# b10n1c.net
KiCad netlist of a schematic drawn in EAGLE
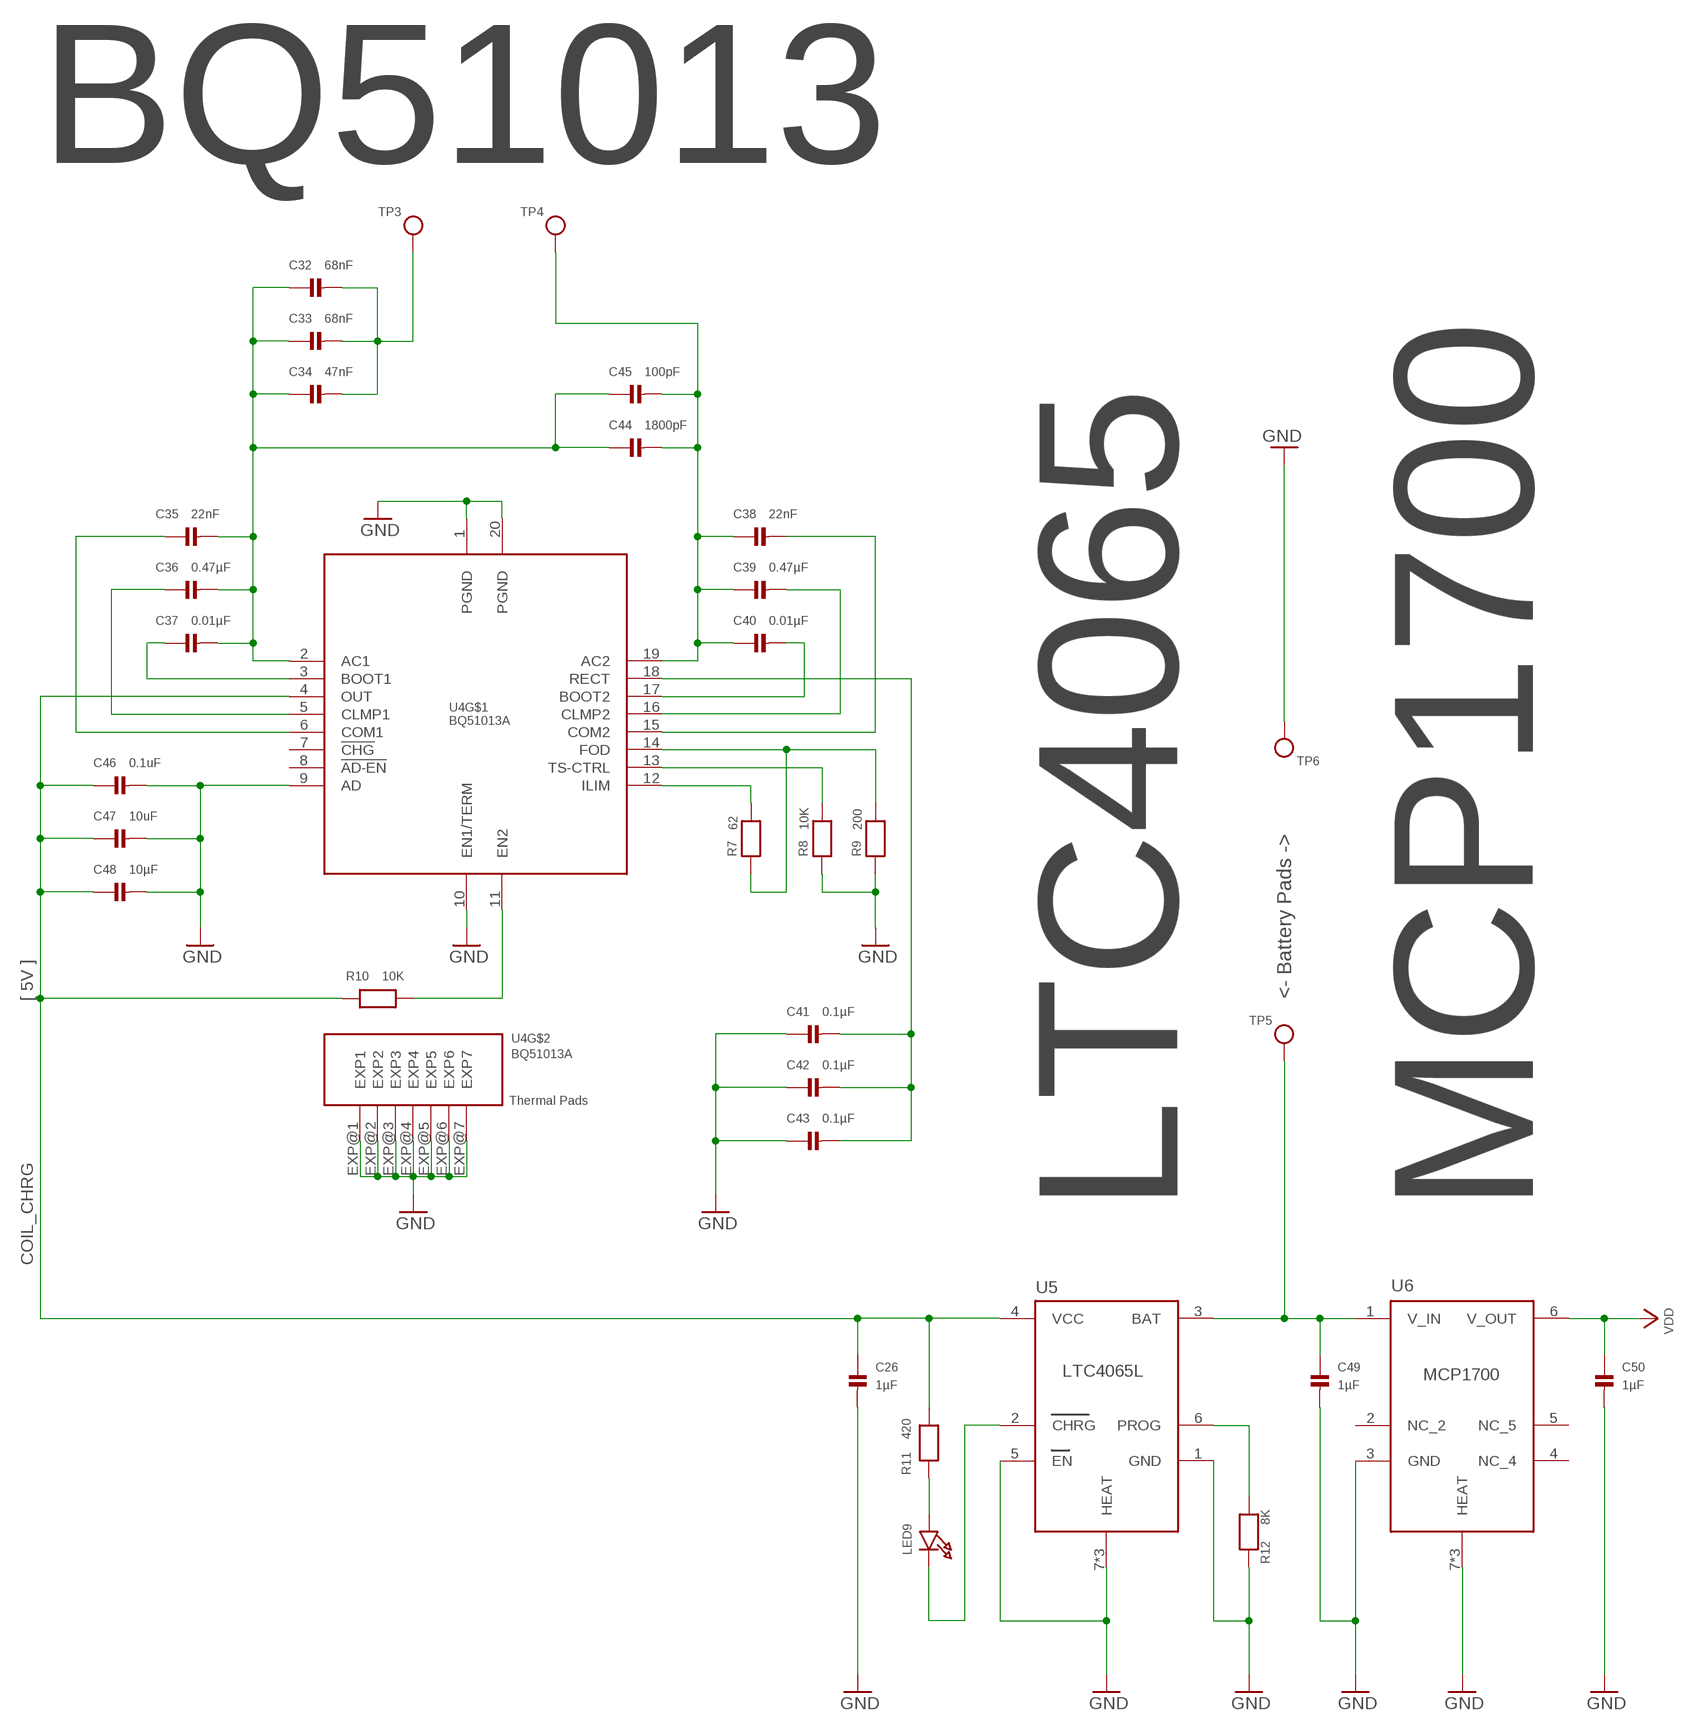
[diagram p0: schematic, sheet 1, part 1 of 2]
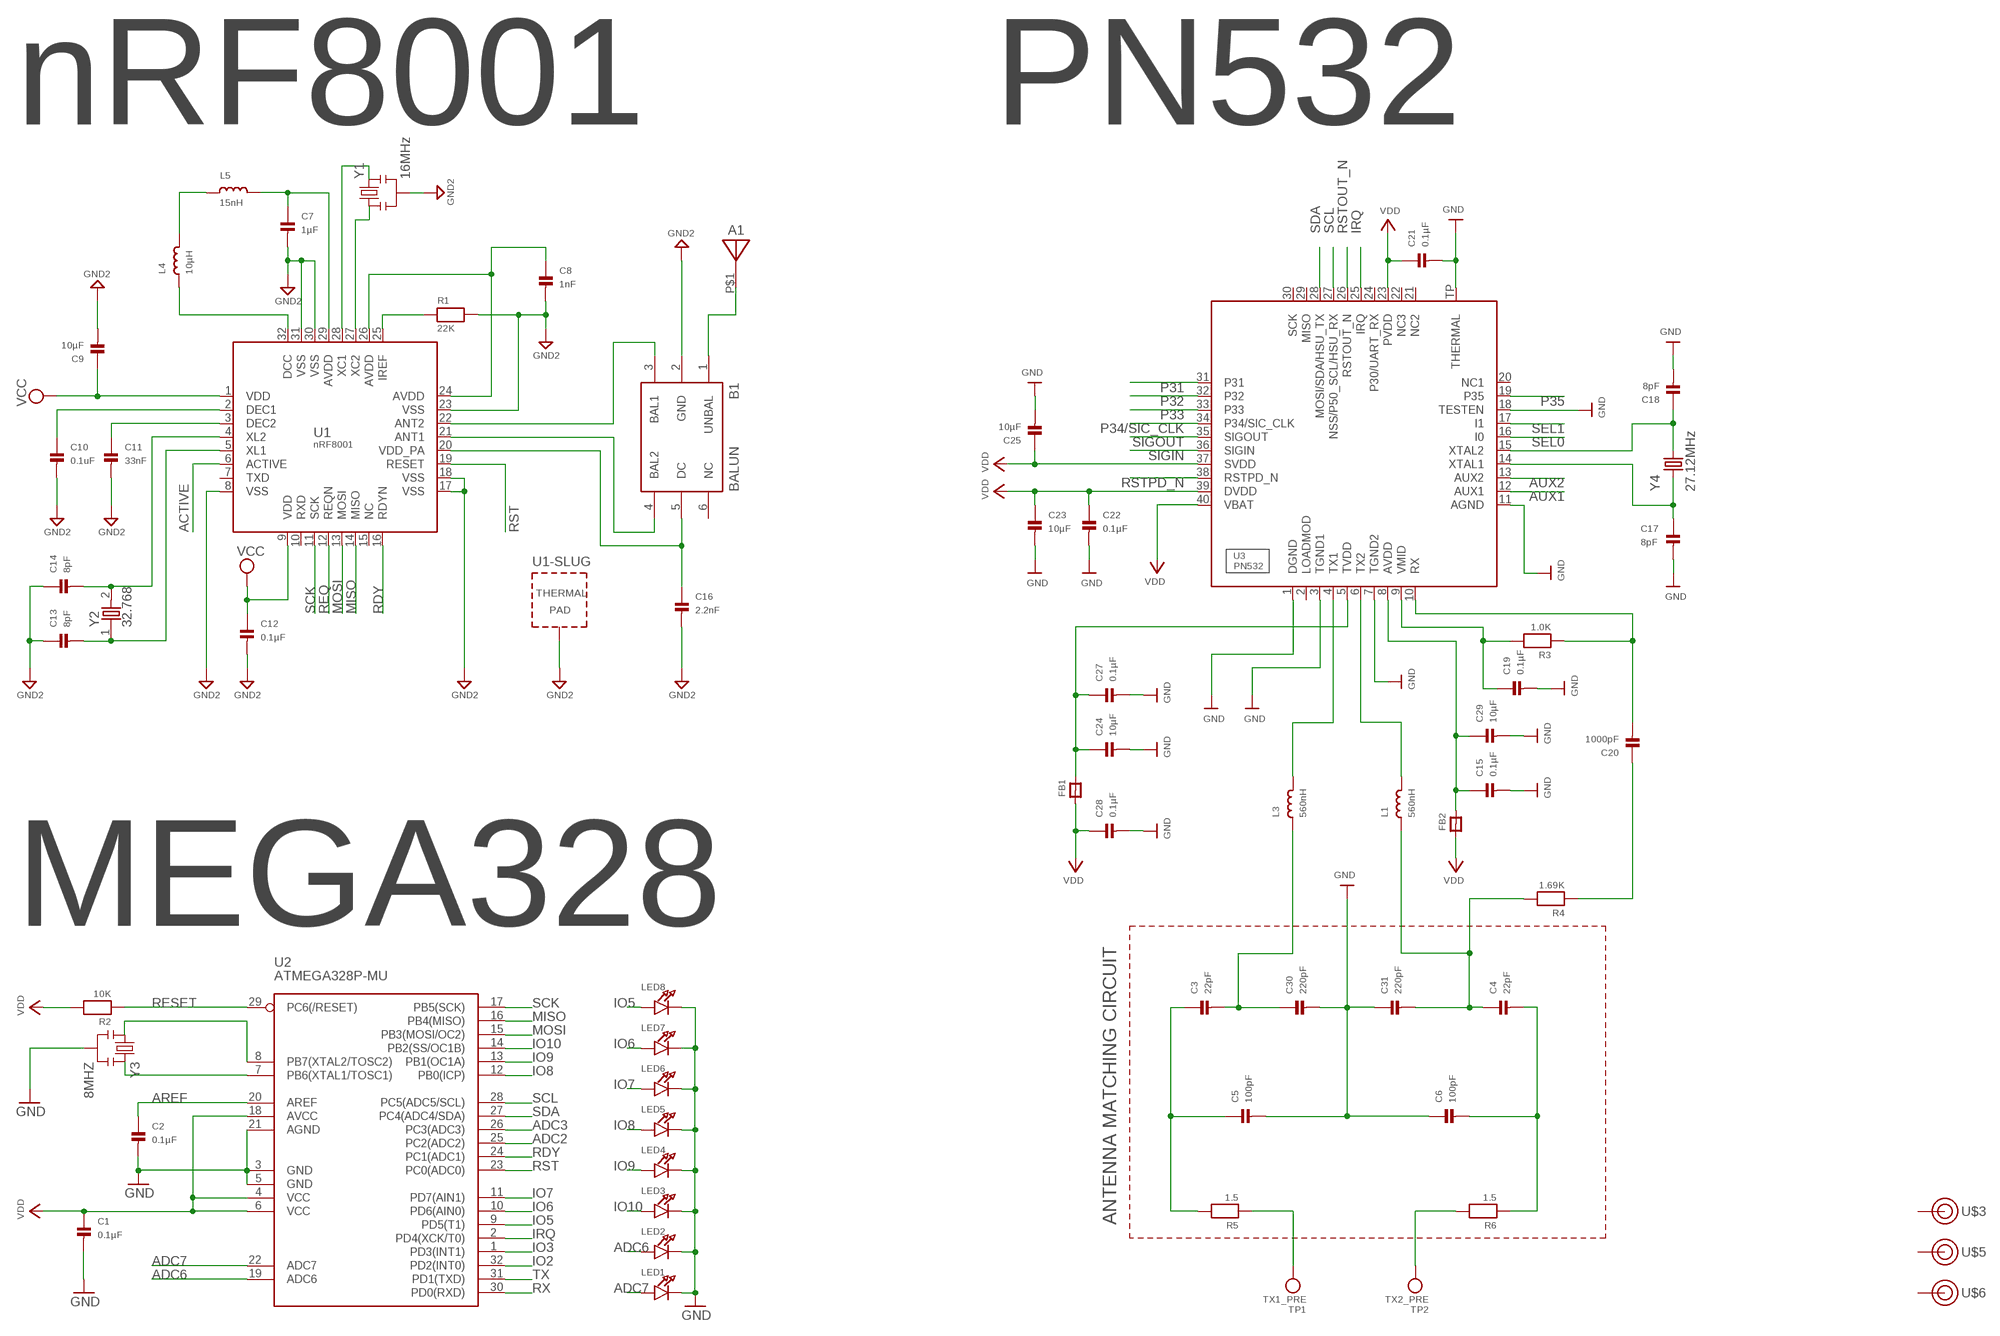
[diagram p1: schematic, sheet 1, part 2 of 2]

(export (version "E")
  (design (tool "Eeschema 10.0.6"))
  (components
    (comp (ref "A1")
      (value "2450AT18A100")
      (footprint "eagle-import:2450AT18A100")
      (libsource (lib "eagle-import") (part "2450AT18A100"))
    )
    (comp (ref "B1")
      (value "2450BM14A0002T")
      (footprint "eagle-import:2450BM14A0002T")
      (libsource (lib "eagle-import") (part "2450BM14A0002T"))
    )
    (comp (ref "C1")
      (value "0.1µF")
      (footprint "eagle-import:_0402MP")
      (libsource (lib "eagle-import") (part "CAP_CERAMIC_0402MP"))
    )
    (comp (ref "C2")
      (value "0.1µF")
      (footprint "eagle-import:_0402MP")
      (libsource (lib "eagle-import") (part "CAP_CERAMIC_0402MP"))
    )
    (comp (ref "C3")
      (value "22pF")
      (footprint "eagle-import:_0402MP")
      (libsource (lib "eagle-import") (part "CAP_CERAMIC_0402MP"))
    )
    (comp (ref "C4")
      (value "22pF")
      (footprint "eagle-import:_0402MP")
      (libsource (lib "eagle-import") (part "CAP_CERAMIC_0402MP"))
    )
    (comp (ref "C5")
      (value "100pF")
      (footprint "eagle-import:_0402MP")
      (libsource (lib "eagle-import") (part "CAP_CERAMIC_0402MP"))
    )
    (comp (ref "C6")
      (value "100pF")
      (footprint "eagle-import:_0402MP")
      (libsource (lib "eagle-import") (part "CAP_CERAMIC_0402MP"))
    )
    (comp (ref "C7")
      (value "1µF")
      (footprint "eagle-import:_0402MP")
      (libsource (lib "eagle-import") (part "CAP_CERAMIC_0402MP"))
    )
    (comp (ref "C8")
      (value "1nF")
      (footprint "eagle-import:_0402MP")
      (libsource (lib "eagle-import") (part "CAP_CERAMIC_0402MP"))
    )
    (comp (ref "C9")
      (value "10µF")
      (footprint "eagle-import:_0402MP")
      (libsource (lib "eagle-import") (part "CAP_CERAMIC_0402MP"))
    )
    (comp (ref "C10")
      (value "0.1uF")
      (footprint "eagle-import:_0402MP")
      (libsource (lib "eagle-import") (part "CAP_CERAMIC_0402MP"))
    )
    (comp (ref "C11")
      (value "33nF")
      (footprint "eagle-import:_0402MP")
      (libsource (lib "eagle-import") (part "CAP_CERAMIC_0402MP"))
    )
    (comp (ref "C12")
      (value "0.1µF")
      (footprint "eagle-import:_0402MP")
      (libsource (lib "eagle-import") (part "CAP_CERAMIC_0402MP"))
    )
    (comp (ref "C13")
      (value "8pF")
      (footprint "eagle-import:_0402MP")
      (libsource (lib "eagle-import") (part "CAP_CERAMIC_0402MP"))
    )
    (comp (ref "C14")
      (value "8pF")
      (footprint "eagle-import:_0402MP")
      (libsource (lib "eagle-import") (part "CAP_CERAMIC_0402MP"))
    )
    (comp (ref "C15")
      (value "0.1µF")
      (footprint "eagle-import:_0402MP")
      (libsource (lib "eagle-import") (part "CAP_CERAMIC_0402MP"))
    )
    (comp (ref "C16")
      (value "2.2nF")
      (footprint "eagle-import:_0402MP")
      (libsource (lib "eagle-import") (part "CAP_CERAMIC_0402MP"))
    )
    (comp (ref "C17")
      (value "8pF")
      (footprint "eagle-import:_0402MP")
      (libsource (lib "eagle-import") (part "CAP_CERAMIC_0402MP"))
    )
    (comp (ref "C18")
      (value "8pF")
      (footprint "eagle-import:_0402MP")
      (libsource (lib "eagle-import") (part "CAP_CERAMIC_0402MP"))
    )
    (comp (ref "C19")
      (value "0.1µF")
      (footprint "eagle-import:_0402MP")
      (libsource (lib "eagle-import") (part "CAP_CERAMIC_0402MP"))
    )
    (comp (ref "C20")
      (value "1000pF")
      (footprint "eagle-import:_0402MP")
      (libsource (lib "eagle-import") (part "CAP_CERAMIC_0402MP"))
    )
    (comp (ref "C21")
      (value "0.1µF")
      (footprint "eagle-import:_0402MP")
      (libsource (lib "eagle-import") (part "CAP_CERAMIC_0402MP"))
    )
    (comp (ref "C22")
      (value "0.1µF")
      (footprint "eagle-import:_0402MP")
      (libsource (lib "eagle-import") (part "CAP_CERAMIC_0402MP"))
    )
    (comp (ref "C23")
      (value "10µF")
      (footprint "eagle-import:_0402MP")
      (libsource (lib "eagle-import") (part "CAP_CERAMIC_0402MP"))
    )
    (comp (ref "C24")
      (value "10µF")
      (footprint "eagle-import:_0402MP")
      (libsource (lib "eagle-import") (part "CAP_CERAMIC_0402MP"))
    )
    (comp (ref "C25")
      (value "10µF")
      (footprint "eagle-import:_0402MP")
      (libsource (lib "eagle-import") (part "CAP_CERAMIC_0402MP"))
    )
    (comp (ref "C26")
      (value "1µF")
      (footprint "eagle-import:_0402MP")
      (libsource (lib "eagle-import") (part "CAP_CERAMIC_0402MP"))
    )
    (comp (ref "C27")
      (value "0.1µF")
      (footprint "eagle-import:_0402MP")
      (libsource (lib "eagle-import") (part "CAP_CERAMIC_0402MP"))
    )
    (comp (ref "C28")
      (value "0.1µF")
      (footprint "eagle-import:_0402MP")
      (libsource (lib "eagle-import") (part "CAP_CERAMIC_0402MP"))
    )
    (comp (ref "C29")
      (value "10µF")
      (footprint "eagle-import:_0402MP")
      (libsource (lib "eagle-import") (part "CAP_CERAMIC_0402MP"))
    )
    (comp (ref "C30")
      (value "220pF")
      (footprint "eagle-import:_0402MP")
      (libsource (lib "eagle-import") (part "CAP_CERAMIC_0402MP"))
    )
    (comp (ref "C31")
      (value "220pF")
      (footprint "eagle-import:_0402MP")
      (libsource (lib "eagle-import") (part "CAP_CERAMIC_0402MP"))
    )
    (comp (ref "C32")
      (value "68nF")
      (footprint "eagle-import:_0402MP")
      (libsource (lib "eagle-import") (part "CAP_CERAMIC_0402MP"))
    )
    (comp (ref "C33")
      (value "68nF")
      (footprint "eagle-import:_0402MP")
      (libsource (lib "eagle-import") (part "CAP_CERAMIC_0402MP"))
    )
    (comp (ref "C34")
      (value "47nF")
      (footprint "eagle-import:_0402MP")
      (libsource (lib "eagle-import") (part "CAP_CERAMIC_0402MP"))
    )
    (comp (ref "C35")
      (value "22nF")
      (footprint "eagle-import:_0402MP")
      (libsource (lib "eagle-import") (part "CAP_CERAMIC_0402MP"))
    )
    (comp (ref "C36")
      (value "0.47µF")
      (footprint "eagle-import:_0402MP")
      (libsource (lib "eagle-import") (part "CAP_CERAMIC_0402MP"))
    )
    (comp (ref "C37")
      (value "0.01µF")
      (footprint "eagle-import:_0402MP")
      (libsource (lib "eagle-import") (part "CAP_CERAMIC_0402MP"))
    )
    (comp (ref "C38")
      (value "22nF")
      (footprint "eagle-import:_0402MP")
      (libsource (lib "eagle-import") (part "CAP_CERAMIC_0402MP"))
    )
    (comp (ref "C39")
      (value "0.47µF")
      (footprint "eagle-import:_0402MP")
      (libsource (lib "eagle-import") (part "CAP_CERAMIC_0402MP"))
    )
    (comp (ref "C40")
      (value "0.01µF")
      (footprint "eagle-import:_0402MP")
      (libsource (lib "eagle-import") (part "CAP_CERAMIC_0402MP"))
    )
    (comp (ref "C41")
      (value "0.1µF")
      (footprint "eagle-import:_0402MP")
      (libsource (lib "eagle-import") (part "CAP_CERAMIC_0402MP"))
    )
    (comp (ref "C42")
      (value "0.1µF")
      (footprint "eagle-import:_0402MP")
      (libsource (lib "eagle-import") (part "CAP_CERAMIC_0402MP"))
    )
    (comp (ref "C43")
      (value "0.1µF")
      (footprint "eagle-import:_0402MP")
      (libsource (lib "eagle-import") (part "CAP_CERAMIC_0402MP"))
    )
    (comp (ref "C44")
      (value "1800pF")
      (footprint "eagle-import:_0402MP")
      (libsource (lib "eagle-import") (part "CAP_CERAMIC_0402MP"))
    )
    (comp (ref "C45")
      (value "100pF")
      (footprint "eagle-import:_0402MP")
      (libsource (lib "eagle-import") (part "CAP_CERAMIC_0402MP"))
    )
    (comp (ref "C46")
      (value "0.1uF")
      (footprint "eagle-import:_0402MP")
      (libsource (lib "eagle-import") (part "CAP_CERAMIC_0402MP"))
    )
    (comp (ref "C47")
      (value "10uF")
      (footprint "eagle-import:_0402MP")
      (libsource (lib "eagle-import") (part "CAP_CERAMIC_0402MP"))
    )
    (comp (ref "C48")
      (value "10µF")
      (footprint "eagle-import:_0402MP")
      (libsource (lib "eagle-import") (part "CAP_CERAMIC_0402MP"))
    )
    (comp (ref "C49")
      (value "1µF")
      (footprint "eagle-import:_0402MP")
      (libsource (lib "eagle-import") (part "CAP_CERAMIC_0402MP"))
    )
    (comp (ref "C50")
      (value "1µF")
      (footprint "eagle-import:_0402MP")
      (libsource (lib "eagle-import") (part "CAP_CERAMIC_0402MP"))
    )
    (comp (ref "FB1")
      (value "FERRITE_0402MP")
      (footprint "eagle-import:_0402MP")
      (libsource (lib "eagle-import") (part "FERRITE_0402MP"))
    )
    (comp (ref "FB2")
      (value "FERRITE_0402MP")
      (footprint "eagle-import:_0402MP")
      (libsource (lib "eagle-import") (part "FERRITE_0402MP"))
    )
    (comp (ref "L1")
      (value "560nH")
      (footprint "eagle-import:_0402MP")
      (libsource (lib "eagle-import") (part "INDUCTOR_0402MP"))
    )
    (comp (ref "L3")
      (value "560nH")
      (footprint "eagle-import:_0402MP")
      (libsource (lib "eagle-import") (part "INDUCTOR_0402MP"))
    )
    (comp (ref "L4")
      (value "10µH")
      (footprint "eagle-import:_0603MP")
      (libsource (lib "eagle-import") (part "INDUCTOR_0603MP"))
    )
    (comp (ref "L5")
      (value "15nH")
      (footprint "eagle-import:_0402MP")
      (libsource (lib "eagle-import") (part "INDUCTOR_0402MP"))
    )
    (comp (ref "LED1")
      (value "LED0603_NOOUTLINE")
      (footprint "eagle-import:CHIPLED_0603_NOOUTLINE")
      (libsource (lib "eagle-import") (part "LED0603_NOOUTLINE"))
    )
    (comp (ref "LED2")
      (value "LED0603_NOOUTLINE")
      (footprint "eagle-import:CHIPLED_0603_NOOUTLINE")
      (libsource (lib "eagle-import") (part "LED0603_NOOUTLINE"))
    )
    (comp (ref "LED3")
      (value "LED0603_NOOUTLINE")
      (footprint "eagle-import:CHIPLED_0603_NOOUTLINE")
      (libsource (lib "eagle-import") (part "LED0603_NOOUTLINE"))
    )
    (comp (ref "LED4")
      (value "LED0603_NOOUTLINE")
      (footprint "eagle-import:CHIPLED_0603_NOOUTLINE")
      (libsource (lib "eagle-import") (part "LED0603_NOOUTLINE"))
    )
    (comp (ref "LED5")
      (value "LED0603_NOOUTLINE")
      (footprint "eagle-import:CHIPLED_0603_NOOUTLINE")
      (libsource (lib "eagle-import") (part "LED0603_NOOUTLINE"))
    )
    (comp (ref "LED6")
      (value "LED0603_NOOUTLINE")
      (footprint "eagle-import:CHIPLED_0603_NOOUTLINE")
      (libsource (lib "eagle-import") (part "LED0603_NOOUTLINE"))
    )
    (comp (ref "LED7")
      (value "LED0603_NOOUTLINE")
      (footprint "eagle-import:CHIPLED_0603_NOOUTLINE")
      (libsource (lib "eagle-import") (part "LED0603_NOOUTLINE"))
    )
    (comp (ref "LED8")
      (value "LED0603_NOOUTLINE")
      (footprint "eagle-import:CHIPLED_0603_NOOUTLINE")
      (libsource (lib "eagle-import") (part "LED0603_NOOUTLINE"))
    )
    (comp (ref "LED9")
      (value "LED0603_NOOUTLINE")
      (footprint "eagle-import:CHIPLED_0603_NOOUTLINE")
      (libsource (lib "eagle-import") (part "LED0603_NOOUTLINE"))
    )
    (comp (ref "R1")
      (value "22K")
      (footprint "eagle-import:_0402MP")
      (libsource (lib "eagle-import") (part "RESISTOR_0402MP"))
    )
    (comp (ref "R2")
      (value "10K")
      (footprint "eagle-import:_0402MP")
      (libsource (lib "eagle-import") (part "RESISTOR_0402MP"))
    )
    (comp (ref "R3")
      (value "1.0K")
      (footprint "eagle-import:_0402MP")
      (libsource (lib "eagle-import") (part "RESISTOR_0402MP"))
    )
    (comp (ref "R4")
      (value "1.69K")
      (footprint "eagle-import:_0402MP")
      (libsource (lib "eagle-import") (part "RESISTOR_0402MP"))
    )
    (comp (ref "R5")
      (value "1.5")
      (footprint "eagle-import:_0402MP")
      (libsource (lib "eagle-import") (part "RESISTOR_0402MP"))
    )
    (comp (ref "R6")
      (value "1.5")
      (footprint "eagle-import:_0402MP")
      (libsource (lib "eagle-import") (part "RESISTOR_0402MP"))
    )
    (comp (ref "R7")
      (value "62")
      (footprint "eagle-import:_0402MP")
      (libsource (lib "eagle-import") (part "RESISTOR_0402MP"))
    )
    (comp (ref "R8")
      (value "10K")
      (footprint "eagle-import:_0402MP")
      (libsource (lib "eagle-import") (part "RESISTOR_0402MP"))
    )
    (comp (ref "R9")
      (value "200")
      (footprint "eagle-import:_0402MP")
      (libsource (lib "eagle-import") (part "RESISTOR_0402MP"))
    )
    (comp (ref "R10")
      (value "10K")
      (footprint "eagle-import:_0402MP")
      (libsource (lib "eagle-import") (part "RESISTOR_0402MP"))
    )
    (comp (ref "R11")
      (value "420")
      (footprint "eagle-import:_0402MP")
      (libsource (lib "eagle-import") (part "RESISTOR_0402MP"))
    )
    (comp (ref "R12")
      (value "8K")
      (footprint "eagle-import:_0402MP")
      (libsource (lib "eagle-import") (part "RESISTOR_0402MP"))
    )
    (comp (ref "TP1")
      (value "TX1_PRE")
      (footprint "eagle-import:TESTPOINT_ROUND_1MM")
      (libsource (lib "eagle-import") (part "TESTPOINTROUND1MM"))
    )
    (comp (ref "TP2")
      (value "TX2_PRE")
      (footprint "eagle-import:TESTPOINT_ROUND_1MM")
      (libsource (lib "eagle-import") (part "TESTPOINTROUND1MM"))
    )
    (comp (ref "TP3")
      (value "TESTPOINTROUND1MM")
      (footprint "eagle-import:TESTPOINT_ROUND_1MM")
      (libsource (lib "eagle-import") (part "TESTPOINTROUND1MM"))
    )
    (comp (ref "TP4")
      (value "TESTPOINTROUND1MM")
      (footprint "eagle-import:TESTPOINT_ROUND_1MM")
      (libsource (lib "eagle-import") (part "TESTPOINTROUND1MM"))
    )
    (comp (ref "TP5")
      (value "TESTPOINTROUND1MM")
      (footprint "eagle-import:TESTPOINT_ROUND_1MM")
      (libsource (lib "eagle-import") (part "TESTPOINTROUND1MM"))
    )
    (comp (ref "TP6")
      (value "TESTPOINTROUND1MM")
      (footprint "eagle-import:TESTPOINT_ROUND_1MM")
      (libsource (lib "eagle-import") (part "TESTPOINTROUND1MM"))
    )
    (comp (ref "U$3")
      (value "MAKE-UB312-MICRO")
      (footprint "eagle-import:MAKE-UB312-MICRO")
      (libsource (lib "eagle-import") (part "MAKE-UB312-MICRO"))
    )
    (comp (ref "U$5")
      (value "MAKE-UB312-MICRO")
      (footprint "eagle-import:MAKE-UB312-MICRO")
      (libsource (lib "eagle-import") (part "MAKE-UB312-MICRO"))
    )
    (comp (ref "U$6")
      (value "MAKE-UB312-MICRO")
      (footprint "eagle-import:MAKE-UB312-MICRO")
      (libsource (lib "eagle-import") (part "MAKE-UB312-MICRO"))
    )
    (comp (ref "U1")
      (value "nRF8001")
      (footprint "eagle-import:QFN32_5MM")
      (libsource (lib "eagle-import") (part "NRF8001"))
    )
    (comp (ref "U2")
      (value "ATMEGA328P-MU")
      (footprint "eagle-import:MLF32-M1-A")
      (libsource (lib "eagle-import") (part "ATMEGAXX8-MU"))
    )
    (comp (ref "U3")
      (value "PN532")
      (footprint "eagle-import:HVQFN40-6X6")
      (libsource (lib "eagle-import") (part "PN532"))
    )
    (comp (ref "U4")
      (value "BQ51013A")
      (footprint "eagle-import:RHL_R-VQFN-N20")
      (libsource (lib "eagle-import") (part "BQ51013A"))
    )
    (comp (ref "U5")
      (value "LTC4065L")
      (footprint "eagle-import:LTC4065L")
      (libsource (lib "eagle-import") (part "LTC4065L"))
    )
    (comp (ref "U6")
      (value "MCP1700")
      (footprint "eagle-import:MCP1700")
      (libsource (lib "eagle-import") (part "MCP1700"))
    )
    (comp (ref "Y1")
      (value "16MHz")
      (footprint "eagle-import:RESONATOR-SMD")
      (libsource (lib "eagle-import") (part "RESONATOR16MHZ"))
    )
    (comp (ref "Y2")
      (value "32.768")
      (footprint "eagle-import:CRYSTAL-2PIN")
      (libsource (lib "eagle-import") (part "CRYSTAL2PIN"))
    )
    (comp (ref "Y3")
      (value "8MHZ")
      (footprint "eagle-import:RESONATOR-SMD")
      (libsource (lib "eagle-import") (part "RESONATOR8MHZ"))
    )
    (comp (ref "Y4")
      (value "27.12MHz")
      (footprint "eagle-import:CRYSTAL-MURATA-XRCGB27M120F3M00R0")
      (libsource (lib "eagle-import") (part "CRYSTAL"))
    )
  )
  (nets
    (net (code "1") (name "/ACTIVE") (class "Default")
      (node (ref "U1") (pin "6") (pinfunction "ACTIVE_6") (pintype "output"))
    )
    (net (code "2") (name "/ADC2") (class "Default")
      (node (ref "U2") (pin "25") (pinfunction "PC2(ADC2)_25") (pintype "bidirectional"))
    )
    (net (code "3") (name "/ADC3") (class "Default")
      (node (ref "U2") (pin "26") (pinfunction "PC3(ADC3)_26") (pintype "bidirectional"))
    )
    (net (code "4") (name "/ADC6") (class "Default")
      (node (ref "LED2") (pin "A") (pinfunction "A_A") (pintype "passive"))
      (node (ref "U2") (pin "19") (pinfunction "ADC6_19") (pintype "bidirectional"))
    )
    (net (code "5") (name "/ADC7") (class "Default")
      (node (ref "LED1") (pin "A") (pinfunction "A_A") (pintype "passive"))
      (node (ref "U2") (pin "22") (pinfunction "ADC7_22") (pintype "bidirectional"))
    )
    (net (code "6") (name "/AREF") (class "Default")
      (node (ref "C2") (pin "1") (pinfunction "P$1_1") (pintype "passive"))
      (node (ref "U2") (pin "20") (pinfunction "AREF_20") (pintype "bidirectional"))
    )
    (net (code "7") (name "/AUX1") (class "Default")
      (node (ref "U3") (pin "12") (pinfunction "AUX1_12") (pintype "bidirectional"))
    )
    (net (code "8") (name "/AUX2") (class "Default")
      (node (ref "U3") (pin "13") (pinfunction "AUX2_13") (pintype "bidirectional"))
    )
    (net (code "9") (name "/COIL_CHRG") (class "Default")
      (node (ref "C26") (pin "1") (pinfunction "P$1_1") (pintype "passive"))
      (node (ref "C46") (pin "1") (pinfunction "P$1_1") (pintype "passive"))
      (node (ref "C47") (pin "1") (pinfunction "P$1_1") (pintype "passive"))
      (node (ref "C48") (pin "1") (pinfunction "P$1_1") (pintype "passive"))
      (node (ref "R10") (pin "2") (pinfunction "2_2") (pintype "passive"))
      (node (ref "R11") (pin "1") (pinfunction "1_1") (pintype "passive"))
      (node (ref "U4") (pin "4") (pinfunction "OUT_4") (pintype "bidirectional"))
      (node (ref "U5") (pin "4") (pinfunction "VCC_4") (pintype "bidirectional"))
    )
    (net (code "10") (name "/IO2") (class "Default")
      (node (ref "U2") (pin "32") (pinfunction "PD2(INT0)_32") (pintype "bidirectional"))
    )
    (net (code "11") (name "/IO3") (class "Default")
      (node (ref "U2") (pin "1") (pinfunction "PD3(INT1)_1") (pintype "bidirectional"))
    )
    (net (code "12") (name "/IO5") (class "Default")
      (node (ref "LED8") (pin "A") (pinfunction "A_A") (pintype "passive"))
      (node (ref "U2") (pin "9") (pinfunction "PD5(T1)_9") (pintype "bidirectional"))
    )
    (net (code "13") (name "/IO6") (class "Default")
      (node (ref "LED7") (pin "A") (pinfunction "A_A") (pintype "passive"))
      (node (ref "U2") (pin "10") (pinfunction "PD6(AIN0)_10") (pintype "bidirectional"))
    )
    (net (code "14") (name "/IO7") (class "Default")
      (node (ref "LED6") (pin "A") (pinfunction "A_A") (pintype "passive"))
      (node (ref "U2") (pin "11") (pinfunction "PD7(AIN1)_11") (pintype "bidirectional"))
    )
    (net (code "15") (name "/IO8") (class "Default")
      (node (ref "LED5") (pin "A") (pinfunction "A_A") (pintype "passive"))
      (node (ref "U2") (pin "12") (pinfunction "PB0(ICP)_12") (pintype "bidirectional"))
    )
    (net (code "16") (name "/IO9") (class "Default")
      (node (ref "LED4") (pin "A") (pinfunction "A_A") (pintype "passive"))
      (node (ref "U2") (pin "13") (pinfunction "PB1(OC1A)_13") (pintype "bidirectional"))
    )
    (net (code "17") (name "/IO10") (class "Default")
      (node (ref "LED3") (pin "A") (pinfunction "A_A") (pintype "passive"))
      (node (ref "U2") (pin "14") (pinfunction "PB2(SS/OC1B)_14") (pintype "bidirectional"))
    )
    (net (code "18") (name "/IRQ") (class "Default")
      (node (ref "U2") (pin "2") (pinfunction "PD4(XCK/T0)_2") (pintype "bidirectional"))
      (node (ref "U3") (pin "25") (pinfunction "IRQ_25") (pintype "bidirectional"))
    )
    (net (code "19") (name "/MISO") (class "Default")
      (node (ref "U1") (pin "14") (pinfunction "MISO_14") (pintype "output"))
      (node (ref "U2") (pin "16") (pinfunction "PB4(MISO)_16") (pintype "bidirectional"))
    )
    (net (code "20") (name "/MOSI") (class "Default")
      (node (ref "U1") (pin "13") (pinfunction "MOSI_13") (pintype "input"))
      (node (ref "U2") (pin "15") (pinfunction "PB3(MOSI/OC2)_15") (pintype "bidirectional"))
    )
    (net (code "21") (name "/P31") (class "Default")
      (node (ref "U3") (pin "31") (pinfunction "P31_31") (pintype "bidirectional"))
    )
    (net (code "22") (name "/P32") (class "Default")
      (node (ref "U3") (pin "32") (pinfunction "P32_32") (pintype "bidirectional"))
    )
    (net (code "23") (name "/P33") (class "Default")
      (node (ref "U3") (pin "33") (pinfunction "P33_33") (pintype "bidirectional"))
    )
    (net (code "24") (name "/P34{slash}SIC_CLK") (class "Default")
      (node (ref "U3") (pin "34") (pinfunction "P34/SIC_CLK_34") (pintype "bidirectional"))
    )
    (net (code "25") (name "/P35") (class "Default")
      (node (ref "U3") (pin "19") (pinfunction "P35_19") (pintype "bidirectional"))
    )
    (net (code "26") (name "/RDY") (class "Default")
      (node (ref "U1") (pin "16") (pinfunction "RDYN_16") (pintype "output"))
      (node (ref "U2") (pin "24") (pinfunction "PC1(ADC1)_24") (pintype "bidirectional"))
    )
    (net (code "27") (name "/REQ") (class "Default")
      (node (ref "U1") (pin "12") (pinfunction "REQN_12") (pintype "input"))
    )
    (net (code "28") (name "/RESET") (class "Default")
      (node (ref "R2") (pin "1") (pinfunction "1_1") (pintype "passive"))
      (node (ref "U2") (pin "29") (pinfunction "PC6(/RESET)_29") (pintype "bidirectional"))
    )
    (net (code "29") (name "/RST") (class "Default")
      (node (ref "U1") (pin "19") (pinfunction "RESET_19") (pintype "input"))
      (node (ref "U2") (pin "23") (pinfunction "PC0(ADC0)_23") (pintype "bidirectional"))
    )
    (net (code "30") (name "/RSTOUT_N") (class "Default")
      (node (ref "U3") (pin "26") (pinfunction "RSTOUT_N_26") (pintype "bidirectional"))
    )
    (net (code "31") (name "/RSTPD_N") (class "Default")
      (node (ref "U3") (pin "38") (pinfunction "RSTPD_N_38") (pintype "bidirectional"))
    )
    (net (code "32") (name "/RX") (class "Default")
      (node (ref "U2") (pin "30") (pinfunction "PD0(RXD)_30") (pintype "bidirectional"))
    )
    (net (code "33") (name "/SCK") (class "Default")
      (node (ref "U1") (pin "11") (pinfunction "SCK_11") (pintype "input"))
      (node (ref "U2") (pin "17") (pinfunction "PB5(SCK)_17") (pintype "bidirectional"))
    )
    (net (code "34") (name "/SCL") (class "Default")
      (node (ref "U2") (pin "28") (pinfunction "PC5(ADC5/SCL)_28") (pintype "bidirectional"))
      (node (ref "U3") (pin "27") (pinfunction "NSS/P50_SCL/HSU_RX_27") (pintype "bidirectional"))
    )
    (net (code "35") (name "/SDA") (class "Default")
      (node (ref "U2") (pin "27") (pinfunction "PC4(ADC4/SDA)_27") (pintype "bidirectional"))
      (node (ref "U3") (pin "28") (pinfunction "MOSI/SDA/HSU_TX_28") (pintype "bidirectional"))
    )
    (net (code "36") (name "/SEL0") (class "Default")
      (node (ref "U3") (pin "16") (pinfunction "I0_16") (pintype "bidirectional"))
    )
    (net (code "37") (name "/SEL1") (class "Default")
      (node (ref "U3") (pin "17") (pinfunction "I1_17") (pintype "bidirectional"))
    )
    (net (code "38") (name "/SIGIN") (class "Default")
      (node (ref "U3") (pin "36") (pinfunction "SIGIN_36") (pintype "bidirectional"))
    )
    (net (code "39") (name "/SIGOUT") (class "Default")
      (node (ref "U3") (pin "35") (pinfunction "SIGOUT_35") (pintype "bidirectional"))
    )
    (net (code "40") (name "/TX") (class "Default")
      (node (ref "U2") (pin "31") (pinfunction "PD1(TXD)_31") (pintype "bidirectional"))
    )
    (net (code "41") (name "GND") (class "Default")
      (node (ref "C1") (pin "2") (pinfunction "P$2_2") (pintype "passive"))
      (node (ref "C15") (pin "2") (pinfunction "P$2_2") (pintype "passive"))
      (node (ref "C17") (pin "2") (pinfunction "P$2_2") (pintype "passive"))
      (node (ref "C18") (pin "2") (pinfunction "P$2_2") (pintype "passive"))
      (node (ref "C19") (pin "2") (pinfunction "P$2_2") (pintype "passive"))
      (node (ref "C2") (pin "2") (pinfunction "P$2_2") (pintype "passive"))
      (node (ref "C21") (pin "2") (pinfunction "P$2_2") (pintype "passive"))
      (node (ref "C22") (pin "2") (pinfunction "P$2_2") (pintype "passive"))
      (node (ref "C23") (pin "2") (pinfunction "P$2_2") (pintype "passive"))
      (node (ref "C24") (pin "2") (pinfunction "P$2_2") (pintype "passive"))
      (node (ref "C25") (pin "2") (pinfunction "P$2_2") (pintype "passive"))
      (node (ref "C26") (pin "2") (pinfunction "P$2_2") (pintype "passive"))
      (node (ref "C27") (pin "2") (pinfunction "P$2_2") (pintype "passive"))
      (node (ref "C28") (pin "2") (pinfunction "P$2_2") (pintype "passive"))
      (node (ref "C29") (pin "2") (pinfunction "P$2_2") (pintype "passive"))
      (node (ref "C30") (pin "2") (pinfunction "P$2_2") (pintype "passive"))
      (node (ref "C31") (pin "1") (pinfunction "P$1_1") (pintype "passive"))
      (node (ref "C41") (pin "1") (pinfunction "P$1_1") (pintype "passive"))
      (node (ref "C42") (pin "1") (pinfunction "P$1_1") (pintype "passive"))
      (node (ref "C43") (pin "1") (pinfunction "P$1_1") (pintype "passive"))
      (node (ref "C46") (pin "2") (pinfunction "P$2_2") (pintype "passive"))
      (node (ref "C47") (pin "2") (pinfunction "P$2_2") (pintype "passive"))
      (node (ref "C48") (pin "2") (pinfunction "P$2_2") (pintype "passive"))
      (node (ref "C49") (pin "2") (pinfunction "P$2_2") (pintype "passive"))
      (node (ref "C5") (pin "2") (pinfunction "P$2_2") (pintype "passive"))
      (node (ref "C50") (pin "2") (pinfunction "P$2_2") (pintype "passive"))
      (node (ref "C6") (pin "1") (pinfunction "P$1_1") (pintype "passive"))
      (node (ref "LED1") (pin "C") (pinfunction "C_C") (pintype "passive"))
      (node (ref "LED2") (pin "C") (pinfunction "C_C") (pintype "passive"))
      (node (ref "LED3") (pin "C") (pinfunction "C_C") (pintype "passive"))
      (node (ref "LED4") (pin "C") (pinfunction "C_C") (pintype "passive"))
      (node (ref "LED5") (pin "C") (pinfunction "C_C") (pintype "passive"))
      (node (ref "LED6") (pin "C") (pinfunction "C_C") (pintype "passive"))
      (node (ref "LED7") (pin "C") (pinfunction "C_C") (pintype "passive"))
      (node (ref "LED8") (pin "C") (pinfunction "C_C") (pintype "passive"))
      (node (ref "R12") (pin "2") (pinfunction "2_2") (pintype "passive"))
      (node (ref "R8") (pin "1") (pinfunction "1_1") (pintype "passive"))
      (node (ref "R9") (pin "1") (pinfunction "1_1") (pintype "passive"))
      (node (ref "TP6") (pin "P$1") (pinfunction "P$1_P$1") (pintype "bidirectional"))
      (node (ref "U2") (pin "21") (pinfunction "AGND_21") (pintype "bidirectional"))
      (node (ref "U2") (pin "3") (pinfunction "GND_3") (pintype "bidirectional"))
      (node (ref "U2") (pin "5") (pinfunction "GND_5") (pintype "bidirectional"))
      (node (ref "U3") (pin "1") (pinfunction "DGND_1") (pintype "bidirectional"))
      (node (ref "U3") (pin "11") (pinfunction "AGND_11") (pintype "bidirectional"))
      (node (ref "U3") (pin "18") (pinfunction "TESTEN_18") (pintype "bidirectional"))
      (node (ref "U3") (pin "3") (pinfunction "TGND1_3") (pintype "bidirectional"))
      (node (ref "U3") (pin "7") (pinfunction "TGND2_7") (pintype "bidirectional"))
      (node (ref "U3") (pin "TP") (pinfunction "THERMAL_TP") (pintype "bidirectional"))
      (node (ref "U4") (pin "1") (pinfunction "PGND_1") (pintype "bidirectional"))
      (node (ref "U4") (pin "10") (pinfunction "EN1/TERM_10") (pintype "bidirectional"))
      (node (ref "U4") (pin "20") (pinfunction "PGND_20") (pintype "bidirectional"))
      (node (ref "U4") (pin "9") (pinfunction "AD_9") (pintype "bidirectional"))
      (node (ref "U4") (pin "EXP@1") (pinfunction "EXP1_EXP@1") (pintype "bidirectional"))
      (node (ref "U4") (pin "EXP@2") (pinfunction "EXP2_EXP@2") (pintype "bidirectional"))
      (node (ref "U4") (pin "EXP@3") (pinfunction "EXP3_EXP@3") (pintype "bidirectional"))
      (node (ref "U4") (pin "EXP@4") (pinfunction "EXP4_EXP@4") (pintype "bidirectional"))
      (node (ref "U4") (pin "EXP@5") (pinfunction "EXP5_EXP@5") (pintype "bidirectional"))
      (node (ref "U4") (pin "EXP@6") (pinfunction "EXP6_EXP@6") (pintype "bidirectional"))
      (node (ref "U4") (pin "EXP@7") (pinfunction "EXP7_EXP@7") (pintype "bidirectional"))
      (node (ref "U5") (pin "1") (pinfunction "GND_1") (pintype "bidirectional"))
      (node (ref "U5") (pin "5") (pinfunction "EN_5") (pintype "bidirectional"))
      (node (ref "U5") (pin "7") (pinfunction "HEAT_7") (pintype "bidirectional"))
      (node (ref "U5") (pin "71") (pinfunction "HEAT_71") (pintype "bidirectional"))
      (node (ref "U5") (pin "72") (pinfunction "HEAT_72") (pintype "bidirectional"))
      (node (ref "U6") (pin "3") (pinfunction "GND_3") (pintype "bidirectional"))
      (node (ref "U6") (pin "7") (pinfunction "HEAT_7") (pintype "bidirectional"))
      (node (ref "U6") (pin "71") (pinfunction "HEAT_71") (pintype "bidirectional"))
      (node (ref "U6") (pin "72") (pinfunction "HEAT_72") (pintype "bidirectional"))
      (node (ref "Y3") (pin "2") (pinfunction "2_2") (pintype "passive"))
    )
    (net (code "42") (name "GND2") (class "Default")
      (node (ref "B1") (pin "2") (pinfunction "GND_2") (pintype "bidirectional"))
      (node (ref "C10") (pin "2") (pinfunction "P$2_2") (pintype "passive"))
      (node (ref "C11") (pin "2") (pinfunction "P$2_2") (pintype "passive"))
      (node (ref "C12") (pin "2") (pinfunction "P$2_2") (pintype "passive"))
      (node (ref "C13") (pin "1") (pinfunction "P$1_1") (pintype "passive"))
      (node (ref "C14") (pin "1") (pinfunction "P$1_1") (pintype "passive"))
      (node (ref "C16") (pin "2") (pinfunction "P$2_2") (pintype "passive"))
      (node (ref "C7") (pin "2") (pinfunction "P$2_2") (pintype "passive"))
      (node (ref "C8") (pin "2") (pinfunction "P$2_2") (pintype "passive"))
      (node (ref "C9") (pin "2") (pinfunction "P$2_2") (pintype "passive"))
      (node (ref "R1") (pin "2") (pinfunction "2_2") (pintype "passive"))
      (node (ref "U1") (pin "17") (pinfunction "VSS_17") (pintype "power_in"))
      (node (ref "U1") (pin "18") (pinfunction "VSS_18") (pintype "power_in"))
      (node (ref "U1") (pin "23") (pinfunction "VSS_23") (pintype "power_in"))
      (node (ref "U1") (pin "30") (pinfunction "VSS_30") (pintype "power_in"))
      (node (ref "U1") (pin "31") (pinfunction "VSS_31") (pintype "power_in"))
      (node (ref "U1") (pin "33") (pinfunction "TP_33") (pintype "power_in"))
      (node (ref "U1") (pin "8") (pinfunction "VSS_8") (pintype "power_in"))
      (node (ref "Y1") (pin "2") (pinfunction "2_2") (pintype "passive"))
    )
    (net (code "43") (name "Net-(B1-BAL1)") (class "Default")
      (node (ref "B1") (pin "3") (pinfunction "BAL1_3") (pintype "bidirectional"))
      (node (ref "U1") (pin "22") (pinfunction "ANT2_22") (pintype "bidirectional"))
    )
    (net (code "44") (name "Net-(B1-BAL2)") (class "Default")
      (node (ref "B1") (pin "4") (pinfunction "BAL2_4") (pintype "bidirectional"))
      (node (ref "U1") (pin "21") (pinfunction "ANT1_21") (pintype "bidirectional"))
    )
    (net (code "45") (name "Net-(B1-DC)") (class "Default")
      (node (ref "B1") (pin "5") (pinfunction "DC_5") (pintype "bidirectional"))
      (node (ref "C16") (pin "1") (pinfunction "P$1_1") (pintype "passive"))
      (node (ref "U1") (pin "20") (pinfunction "VDD_PA_20") (pintype "bidirectional"))
    )
    (net (code "46") (name "Net-(B1-UNBAL)") (class "Default")
      (node (ref "A1") (pin "P$1") (pinfunction "P$1_P$1") (pintype "bidirectional"))
      (node (ref "B1") (pin "1") (pinfunction "UNBAL_1") (pintype "bidirectional"))
    )
    (net (code "47") (name "Net-(C3-P$1)") (class "Default")
      (node (ref "C3") (pin "1") (pinfunction "P$1_1") (pintype "passive"))
      (node (ref "C5") (pin "1") (pinfunction "P$1_1") (pintype "passive"))
      (node (ref "R5") (pin "2") (pinfunction "2_2") (pintype "passive"))
    )
    (net (code "48") (name "Net-(C3-P$2)") (class "Default")
      (node (ref "C3") (pin "2") (pinfunction "P$2_2") (pintype "passive"))
      (node (ref "C30") (pin "1") (pinfunction "P$1_1") (pintype "passive"))
      (node (ref "L3") (pin "1") (pinfunction "1_1") (pintype "passive"))
    )
    (net (code "49") (name "Net-(C4-P$2)") (class "Default")
      (node (ref "C4") (pin "2") (pinfunction "P$2_2") (pintype "passive"))
      (node (ref "C6") (pin "2") (pinfunction "P$2_2") (pintype "passive"))
      (node (ref "R6") (pin "1") (pinfunction "1_1") (pintype "passive"))
    )
    (net (code "50") (name "Net-(C7-P$1)") (class "Default")
      (node (ref "C7") (pin "1") (pinfunction "P$1_1") (pintype "passive"))
      (node (ref "L5") (pin "2") (pinfunction "2_2") (pintype "passive"))
      (node (ref "U1") (pin "29") (pinfunction "AVDD_29") (pintype "power_in"))
    )
    (net (code "51") (name "Net-(C8-P$1)") (class "Default")
      (node (ref "C8") (pin "1") (pinfunction "P$1_1") (pintype "passive"))
      (node (ref "U1") (pin "24") (pinfunction "AVDD_24") (pintype "power_in"))
      (node (ref "U1") (pin "26") (pinfunction "AVDD_26") (pintype "power_in"))
    )
    (net (code "52") (name "Net-(C10-P$1)") (class "Default")
      (node (ref "C10") (pin "1") (pinfunction "P$1_1") (pintype "passive"))
      (node (ref "U1") (pin "2") (pinfunction "DEC1_2") (pintype "bidirectional"))
    )
    (net (code "53") (name "Net-(C11-P$1)") (class "Default")
      (node (ref "C11") (pin "1") (pinfunction "P$1_1") (pintype "passive"))
      (node (ref "U1") (pin "3") (pinfunction "DEC2_3") (pintype "bidirectional"))
    )
    (net (code "54") (name "Net-(C13-P$2)") (class "Default")
      (node (ref "C13") (pin "2") (pinfunction "P$2_2") (pintype "passive"))
      (node (ref "U1") (pin "5") (pinfunction "XL1_5") (pintype "input"))
      (node (ref "Y2") (pin "1") (pinfunction "1_1") (pintype "passive"))
    )
    (net (code "55") (name "Net-(C14-P$2)") (class "Default")
      (node (ref "C14") (pin "2") (pinfunction "P$2_2") (pintype "passive"))
      (node (ref "U1") (pin "4") (pinfunction "XL2_4") (pintype "output"))
      (node (ref "Y2") (pin "2") (pinfunction "2_2") (pintype "passive"))
    )
    (net (code "56") (name "Net-(C15-P$1)") (class "Default")
      (node (ref "C15") (pin "1") (pinfunction "P$1_1") (pintype "passive"))
      (node (ref "C29") (pin "1") (pinfunction "P$1_1") (pintype "passive"))
      (node (ref "FB2") (pin "2") (pinfunction "P$2_2") (pintype "passive"))
      (node (ref "U3") (pin "8") (pinfunction "AVDD_8") (pintype "bidirectional"))
    )
    (net (code "57") (name "Net-(C17-P$1)") (class "Default")
      (node (ref "C17") (pin "1") (pinfunction "P$1_1") (pintype "passive"))
      (node (ref "U3") (pin "14") (pinfunction "XTAL1_14") (pintype "bidirectional"))
      (node (ref "Y4") (pin "1") (pinfunction "1_1") (pintype "passive"))
    )
    (net (code "58") (name "Net-(C18-P$1)") (class "Default")
      (node (ref "C18") (pin "1") (pinfunction "P$1_1") (pintype "passive"))
      (node (ref "U3") (pin "15") (pinfunction "XTAL2_15") (pintype "bidirectional"))
      (node (ref "Y4") (pin "3") (pinfunction "2_3") (pintype "passive"))
    )
    (net (code "59") (name "Net-(C19-P$1)") (class "Default")
      (node (ref "C19") (pin "1") (pinfunction "P$1_1") (pintype "passive"))
      (node (ref "R3") (pin "2") (pinfunction "2_2") (pintype "passive"))
      (node (ref "U3") (pin "9") (pinfunction "VMID_9") (pintype "bidirectional"))
    )
    (net (code "60") (name "Net-(C20-P$1)") (class "Default")
      (node (ref "C20") (pin "1") (pinfunction "P$1_1") (pintype "passive"))
      (node (ref "R4") (pin "1") (pinfunction "1_1") (pintype "passive"))
    )
    (net (code "61") (name "Net-(C20-P$2)") (class "Default")
      (node (ref "C20") (pin "2") (pinfunction "P$2_2") (pintype "passive"))
      (node (ref "R3") (pin "1") (pinfunction "1_1") (pintype "passive"))
      (node (ref "U3") (pin "10") (pinfunction "RX_10") (pintype "bidirectional"))
    )
    (net (code "62") (name "Net-(C24-P$1)") (class "Default")
      (node (ref "C24") (pin "1") (pinfunction "P$1_1") (pintype "passive"))
      (node (ref "C27") (pin "1") (pinfunction "P$1_1") (pintype "passive"))
      (node (ref "FB1") (pin "2") (pinfunction "P$2_2") (pintype "passive"))
      (node (ref "U3") (pin "5") (pinfunction "TVDD_5") (pintype "bidirectional"))
    )
    (net (code "63") (name "Net-(C31-P$2)") (class "Default")
      (node (ref "C31") (pin "2") (pinfunction "P$2_2") (pintype "passive"))
      (node (ref "C4") (pin "1") (pinfunction "P$1_1") (pintype "passive"))
      (node (ref "L1") (pin "1") (pinfunction "1_1") (pintype "passive"))
      (node (ref "R4") (pin "2") (pinfunction "2_2") (pintype "passive"))
    )
    (net (code "64") (name "Net-(C32-P$1)") (class "Default")
      (node (ref "C32") (pin "1") (pinfunction "P$1_1") (pintype "passive"))
      (node (ref "C33") (pin "1") (pinfunction "P$1_1") (pintype "passive"))
      (node (ref "C34") (pin "1") (pinfunction "P$1_1") (pintype "passive"))
      (node (ref "C35") (pin "2") (pinfunction "P$2_2") (pintype "passive"))
      (node (ref "C36") (pin "2") (pinfunction "P$2_2") (pintype "passive"))
      (node (ref "C37") (pin "2") (pinfunction "P$2_2") (pintype "passive"))
      (node (ref "C44") (pin "1") (pinfunction "P$1_1") (pintype "passive"))
      (node (ref "C45") (pin "1") (pinfunction "P$1_1") (pintype "passive"))
      (node (ref "U4") (pin "2") (pinfunction "AC1_2") (pintype "bidirectional"))
    )
    (net (code "65") (name "Net-(C32-P$2)") (class "Default")
      (node (ref "C32") (pin "2") (pinfunction "P$2_2") (pintype "passive"))
      (node (ref "C33") (pin "2") (pinfunction "P$2_2") (pintype "passive"))
      (node (ref "C34") (pin "2") (pinfunction "P$2_2") (pintype "passive"))
      (node (ref "TP3") (pin "P$1") (pinfunction "P$1_P$1") (pintype "bidirectional"))
    )
    (net (code "66") (name "Net-(C35-P$1)") (class "Default")
      (node (ref "C35") (pin "1") (pinfunction "P$1_1") (pintype "passive"))
      (node (ref "U4") (pin "6") (pinfunction "COM1_6") (pintype "bidirectional"))
    )
    (net (code "67") (name "Net-(C36-P$1)") (class "Default")
      (node (ref "C36") (pin "1") (pinfunction "P$1_1") (pintype "passive"))
      (node (ref "U4") (pin "5") (pinfunction "CLMP1_5") (pintype "bidirectional"))
    )
    (net (code "68") (name "Net-(C37-P$1)") (class "Default")
      (node (ref "C37") (pin "1") (pinfunction "P$1_1") (pintype "passive"))
      (node (ref "U4") (pin "3") (pinfunction "BOOT1_3") (pintype "bidirectional"))
    )
    (net (code "69") (name "Net-(C38-P$1)") (class "Default")
      (node (ref "C38") (pin "1") (pinfunction "P$1_1") (pintype "passive"))
      (node (ref "C39") (pin "1") (pinfunction "P$1_1") (pintype "passive"))
      (node (ref "C40") (pin "1") (pinfunction "P$1_1") (pintype "passive"))
      (node (ref "C44") (pin "2") (pinfunction "P$2_2") (pintype "passive"))
      (node (ref "C45") (pin "2") (pinfunction "P$2_2") (pintype "passive"))
      (node (ref "TP4") (pin "P$1") (pinfunction "P$1_P$1") (pintype "bidirectional"))
      (node (ref "U4") (pin "19") (pinfunction "AC2_19") (pintype "bidirectional"))
    )
    (net (code "70") (name "Net-(C38-P$2)") (class "Default")
      (node (ref "C38") (pin "2") (pinfunction "P$2_2") (pintype "passive"))
      (node (ref "U4") (pin "15") (pinfunction "COM2_15") (pintype "bidirectional"))
    )
    (net (code "71") (name "Net-(C39-P$2)") (class "Default")
      (node (ref "C39") (pin "2") (pinfunction "P$2_2") (pintype "passive"))
      (node (ref "U4") (pin "16") (pinfunction "CLMP2_16") (pintype "bidirectional"))
    )
    (net (code "72") (name "Net-(C40-P$2)") (class "Default")
      (node (ref "C40") (pin "2") (pinfunction "P$2_2") (pintype "passive"))
      (node (ref "U4") (pin "17") (pinfunction "BOOT2_17") (pintype "bidirectional"))
    )
    (net (code "73") (name "Net-(C41-P$2)") (class "Default")
      (node (ref "C41") (pin "2") (pinfunction "P$2_2") (pintype "passive"))
      (node (ref "C42") (pin "2") (pinfunction "P$2_2") (pintype "passive"))
      (node (ref "C43") (pin "2") (pinfunction "P$2_2") (pintype "passive"))
      (node (ref "U4") (pin "18") (pinfunction "RECT_18") (pintype "bidirectional"))
    )
    (net (code "74") (name "Net-(C49-P$1)") (class "Default")
      (node (ref "C49") (pin "1") (pinfunction "P$1_1") (pintype "passive"))
      (node (ref "TP5") (pin "P$1") (pinfunction "P$1_P$1") (pintype "bidirectional"))
      (node (ref "U5") (pin "3") (pinfunction "BAT_3") (pintype "bidirectional"))
      (node (ref "U6") (pin "1") (pinfunction "V_IN_1") (pintype "bidirectional"))
    )
    (net (code "75") (name "Net-(L4-Pad2)") (class "Default")
      (node (ref "L4") (pin "2") (pinfunction "2_2") (pintype "passive"))
      (node (ref "L5") (pin "1") (pinfunction "1_1") (pintype "passive"))
    )
    (net (code "76") (name "Net-(LED9-PadA)") (class "Default")
      (node (ref "LED9") (pin "A") (pinfunction "A_A") (pintype "passive"))
      (node (ref "R11") (pin "2") (pinfunction "2_2") (pintype "passive"))
    )
    (net (code "77") (name "Net-(R5-Pad1)") (class "Default")
      (node (ref "R5") (pin "1") (pinfunction "1_1") (pintype "passive"))
      (node (ref "TP1") (pin "P$1") (pinfunction "P$1_P$1") (pintype "bidirectional"))
    )
    (net (code "78") (name "Net-(R6-Pad2)") (class "Default")
      (node (ref "R6") (pin "2") (pinfunction "2_2") (pintype "passive"))
      (node (ref "TP2") (pin "P$1") (pinfunction "P$1_P$1") (pintype "bidirectional"))
    )
    (net (code "79") (name "Net-(U1B-DCC)") (class "Default")
      (node (ref "L4") (pin "1") (pinfunction "1_1") (pintype "passive"))
      (node (ref "U1") (pin "32") (pinfunction "DCC_32") (pintype "bidirectional"))
    )
    (net (code "80") (name "Net-(U1B-IREF)") (class "Default")
      (node (ref "R1") (pin "1") (pinfunction "1_1") (pintype "passive"))
      (node (ref "U1") (pin "25") (pinfunction "IREF_25") (pintype "output"))
    )
    (net (code "81") (name "Net-(U1B-XC1)") (class "Default")
      (node (ref "U1") (pin "28") (pinfunction "XC1_28") (pintype "input"))
      (node (ref "Y1") (pin "3") (pinfunction "3_3") (pintype "passive"))
    )
    (net (code "82") (name "Net-(U1B-XC2)") (class "Default")
      (node (ref "U1") (pin "27") (pinfunction "XC2_27") (pintype "output"))
      (node (ref "Y1") (pin "1") (pinfunction "1_1") (pintype "passive"))
    )
    (net (code "83") (name "Net-(U2-PB6(XTAL1{slash}TOSC1))") (class "Default")
      (node (ref "U2") (pin "7") (pinfunction "PB6(XTAL1/TOSC1)_7") (pintype "bidirectional"))
      (node (ref "Y3") (pin "3") (pinfunction "3_3") (pintype "passive"))
    )
    (net (code "84") (name "Net-(U2-PB7(XTAL2{slash}TOSC2))") (class "Default")
      (node (ref "U2") (pin "8") (pinfunction "PB7(XTAL2/TOSC2)_8") (pintype "bidirectional"))
      (node (ref "Y3") (pin "1") (pinfunction "1_1") (pintype "passive"))
    )
    (net (code "85") (name "Net-(U3-TX1)") (class "Default")
      (node (ref "L3") (pin "2") (pinfunction "2_2") (pintype "passive"))
      (node (ref "U3") (pin "4") (pinfunction "TX1_4") (pintype "bidirectional"))
    )
    (net (code "86") (name "Net-(U3-TX2)") (class "Default")
      (node (ref "L1") (pin "2") (pinfunction "2_2") (pintype "passive"))
      (node (ref "U3") (pin "6") (pinfunction "TX2_6") (pintype "bidirectional"))
    )
    (net (code "87") (name "Net-(U4A-EN2)") (class "Default")
      (node (ref "R10") (pin "1") (pinfunction "1_1") (pintype "passive"))
      (node (ref "U4") (pin "11") (pinfunction "EN2_11") (pintype "bidirectional"))
    )
    (net (code "88") (name "Net-(U4A-FOD)") (class "Default")
      (node (ref "R7") (pin "1") (pinfunction "1_1") (pintype "passive"))
      (node (ref "R9") (pin "2") (pinfunction "2_2") (pintype "passive"))
      (node (ref "U4") (pin "14") (pinfunction "FOD_14") (pintype "bidirectional"))
    )
    (net (code "89") (name "Net-(U4A-ILIM)") (class "Default")
      (node (ref "R7") (pin "2") (pinfunction "2_2") (pintype "passive"))
      (node (ref "U4") (pin "12") (pinfunction "ILIM_12") (pintype "bidirectional"))
    )
    (net (code "90") (name "Net-(U4A-TS-CTRL)") (class "Default")
      (node (ref "R8") (pin "2") (pinfunction "2_2") (pintype "passive"))
      (node (ref "U4") (pin "13") (pinfunction "TS-CTRL_13") (pintype "bidirectional"))
    )
    (net (code "91") (name "Net-(U5-CHRG)") (class "Default")
      (node (ref "LED9") (pin "C") (pinfunction "C_C") (pintype "passive"))
      (node (ref "U5") (pin "2") (pinfunction "CHRG_2") (pintype "bidirectional"))
    )
    (net (code "92") (name "Net-(U5-PROG)") (class "Default")
      (node (ref "R12") (pin "1") (pinfunction "1_1") (pintype "passive"))
      (node (ref "U5") (pin "6") (pinfunction "PROG_6") (pintype "bidirectional"))
    )
    (net (code "93") (name "VCC") (class "Default")
      (node (ref "C12") (pin "1") (pinfunction "P$1_1") (pintype "passive"))
      (node (ref "C9") (pin "1") (pinfunction "P$1_1") (pintype "passive"))
      (node (ref "U1") (pin "1") (pinfunction "VDD_1") (pintype "power_in"))
      (node (ref "U1") (pin "9") (pinfunction "VDD_9") (pintype "power_in"))
    )
    (net (code "94") (name "VDD") (class "Default")
      (node (ref "C1") (pin "1") (pinfunction "P$1_1") (pintype "passive"))
      (node (ref "C21") (pin "1") (pinfunction "P$1_1") (pintype "passive"))
      (node (ref "C22") (pin "1") (pinfunction "P$1_1") (pintype "passive"))
      (node (ref "C23") (pin "1") (pinfunction "P$1_1") (pintype "passive"))
      (node (ref "C25") (pin "1") (pinfunction "P$1_1") (pintype "passive"))
      (node (ref "C28") (pin "1") (pinfunction "P$1_1") (pintype "passive"))
      (node (ref "C50") (pin "1") (pinfunction "P$1_1") (pintype "passive"))
      (node (ref "FB1") (pin "1") (pinfunction "P$1_1") (pintype "passive"))
      (node (ref "FB2") (pin "1") (pinfunction "P$1_1") (pintype "passive"))
      (node (ref "R2") (pin "2") (pinfunction "2_2") (pintype "passive"))
      (node (ref "U2") (pin "18") (pinfunction "AVCC_18") (pintype "bidirectional"))
      (node (ref "U2") (pin "4") (pinfunction "VCC_4") (pintype "bidirectional"))
      (node (ref "U2") (pin "6") (pinfunction "VCC_6") (pintype "bidirectional"))
      (node (ref "U3") (pin "23") (pinfunction "PVDD_23") (pintype "bidirectional"))
      (node (ref "U3") (pin "37") (pinfunction "SVDD_37") (pintype "bidirectional"))
      (node (ref "U3") (pin "39") (pinfunction "DVDD_39") (pintype "bidirectional"))
      (node (ref "U3") (pin "40") (pinfunction "VBAT_40") (pintype "bidirectional"))
      (node (ref "U6") (pin "6") (pinfunction "V_OUT_6") (pintype "bidirectional"))
    )
    (net (code "95") (name "unconnected-(B1-NC-Pad6)") (class "Default")
      (node (ref "B1") (pin "6") (pinfunction "NC_6") (pintype "bidirectional"))
    )
    (net (code "96") (name "unconnected-(U$3-T-PadP$1)") (class "Default")
      (node (ref "U$3") (pin "P$1") (pinfunction "T_P$1") (pintype "bidirectional"))
    )
    (net (code "97") (name "unconnected-(U$5-T-PadP$1)") (class "Default")
      (node (ref "U$5") (pin "P$1") (pinfunction "T_P$1") (pintype "bidirectional"))
    )
    (net (code "98") (name "unconnected-(U$6-T-PadP$1)") (class "Default")
      (node (ref "U$6") (pin "P$1") (pinfunction "T_P$1") (pintype "bidirectional"))
    )
    (net (code "99") (name "unconnected-(U1B-NC-Pad15)") (class "Default")
      (node (ref "U1") (pin "15") (pinfunction "NC_15") (pintype "no_connect"))
    )
    (net (code "100") (name "unconnected-(U1B-RXD-Pad10)") (class "Default")
      (node (ref "U1") (pin "10") (pinfunction "RXD_10") (pintype "input"))
    )
    (net (code "101") (name "unconnected-(U1B-TXD-Pad7)") (class "Default")
      (node (ref "U1") (pin "7") (pinfunction "TXD_7") (pintype "output"))
    )
    (net (code "102") (name "unconnected-(U3-LOADMOD-Pad2)") (class "Default")
      (node (ref "U3") (pin "2") (pinfunction "LOADMOD_2") (pintype "bidirectional"))
    )
    (net (code "103") (name "unconnected-(U3-MISO-Pad29)") (class "Default")
      (node (ref "U3") (pin "29") (pinfunction "MISO_29") (pintype "bidirectional"))
    )
    (net (code "104") (name "unconnected-(U3-NC1-Pad20)") (class "Default")
      (node (ref "U3") (pin "20") (pinfunction "NC1_20") (pintype "bidirectional"))
    )
    (net (code "105") (name "unconnected-(U3-NC2-Pad21)") (class "Default")
      (node (ref "U3") (pin "21") (pinfunction "NC2_21") (pintype "bidirectional"))
    )
    (net (code "106") (name "unconnected-(U3-NC3-Pad22)") (class "Default")
      (node (ref "U3") (pin "22") (pinfunction "NC3_22") (pintype "bidirectional"))
    )
    (net (code "107") (name "unconnected-(U3-P30{slash}UART_RX-Pad24)") (class "Default")
      (node (ref "U3") (pin "24") (pinfunction "P30/UART_RX_24") (pintype "bidirectional"))
    )
    (net (code "108") (name "unconnected-(U3-SCK-Pad30)") (class "Default")
      (node (ref "U3") (pin "30") (pinfunction "SCK_30") (pintype "bidirectional"))
    )
    (net (code "109") (name "unconnected-(U4A-~{AD-EN}-Pad8)") (class "Default")
      (node (ref "U4") (pin "8") (pinfunction "~{AD-EN}_8") (pintype "bidirectional"))
    )
    (net (code "110") (name "unconnected-(U4A-~{CHG}-Pad7)") (class "Default")
      (node (ref "U4") (pin "7") (pinfunction "~{CHG}_7") (pintype "bidirectional"))
    )
    (net (code "111") (name "unconnected-(U6-NC_2-Pad2)") (class "Default")
      (node (ref "U6") (pin "2") (pinfunction "NC_2_2") (pintype "bidirectional"))
    )
    (net (code "112") (name "unconnected-(U6-NC_4-Pad4)") (class "Default")
      (node (ref "U6") (pin "4") (pinfunction "NC_4_4") (pintype "bidirectional"))
    )
    (net (code "113") (name "unconnected-(U6-NC_5-Pad5)") (class "Default")
      (node (ref "U6") (pin "5") (pinfunction "NC_5_5") (pintype "bidirectional"))
    )
  )
)
